# Current_Sense_-_AMS.net
KiCad netlist of a schematic drawn in Altium Designer
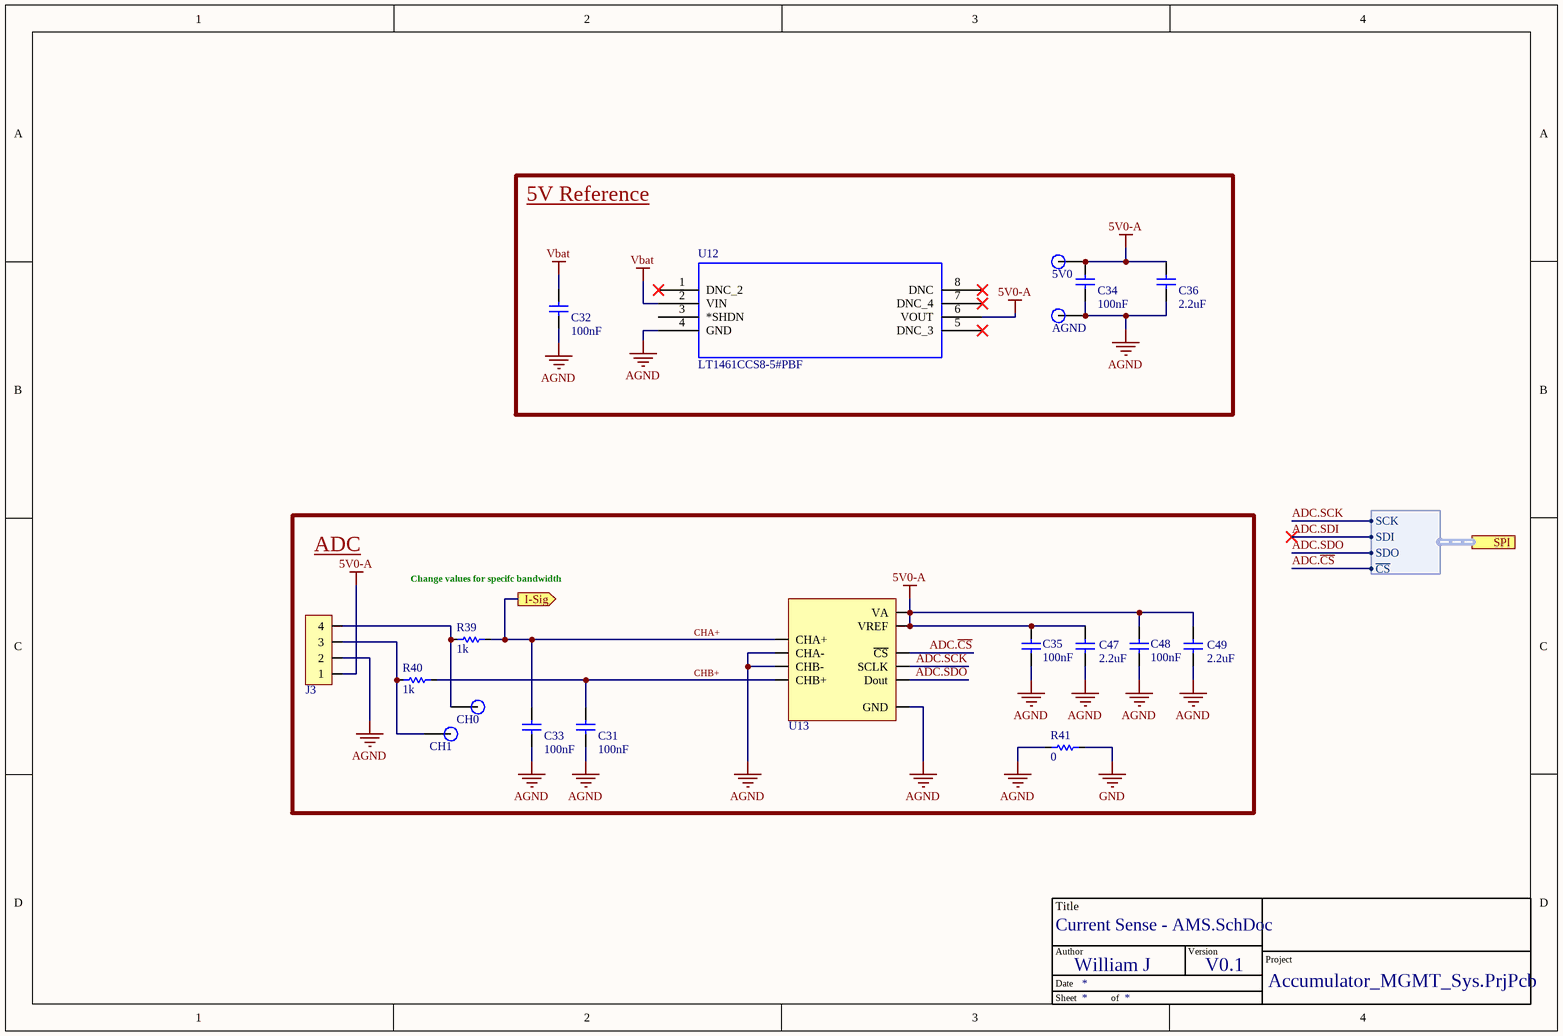
[diagram p0: Current Sense - AMS.SchDoc]

(export (version "E")
  (design (tool "Eeschema 10.0.6"))
  (components
    (comp (ref "5V0")
      (value "1.2mm Test point")
      (footprint "Test Point")
      (libsource (lib "PCHLib") (part "Test Point"))
    )
    (comp (ref "AGND")
      (value "1.2mm Test point")
      (footprint "Test Point")
      (libsource (lib "PCHLib") (part "Test Point"))
    )
    (comp (ref "C31")
      (value "100nF")
      (footprint "0402")
      (description "Capacitor")
      (fields (field (name "Comment") "C0603C104K3RAC7013"))
      (libsource (lib "Passives") (part "Capacitor"))
    )
    (comp (ref "C32")
      (value "100nF")
      (footprint "C_0603")
      (description "Capacitor")
      (fields (field (name "Comment") "C0603C104K3RAC7013"))
      (libsource (lib "Passives") (part "Capacitor"))
    )
    (comp (ref "C33")
      (value "100nF")
      (footprint "0402")
      (description "Capacitor")
      (fields (field (name "Comment") "C0603C104K3RAC7013"))
      (libsource (lib "Passives") (part "Capacitor"))
    )
    (comp (ref "C34")
      (value "100nF")
      (footprint "C_0603")
      (description "Capacitor")
      (fields (field (name "Comment") "C0603C104K3RAC7013"))
      (libsource (lib "Passives") (part "Capacitor"))
    )
    (comp (ref "C35")
      (value "100nF")
      (footprint "C_0603")
      (description "Capacitor")
      (fields (field (name "Comment") "C0603C104K3RAC7013"))
      (libsource (lib "Passives") (part "Capacitor"))
    )
    (comp (ref "C36")
      (value "2.2uF")
      (footprint "C_0603")
      (description "Capacitor")
      (fields (field (name "Comment") "CL10A225KP8NNNC"))
      (libsource (lib "Passives") (part "Capacitor"))
    )
    (comp (ref "C47")
      (value "2.2uF")
      (footprint "C_0603")
      (description "Capacitor")
      (fields (field (name "Comment") "CL10A225KP8NNNC"))
      (libsource (lib "Passives") (part "Capacitor"))
    )
    (comp (ref "C48")
      (value "100nF")
      (footprint "C_0603")
      (description "Capacitor")
      (fields (field (name "Comment") "C0603C104K3RAC7013"))
      (libsource (lib "Passives") (part "Capacitor"))
    )
    (comp (ref "C49")
      (value "2.2uF")
      (footprint "C_0603")
      (description "Capacitor")
      (fields (field (name "Comment") "CL10A225KP8NNNC"))
      (libsource (lib "Passives") (part "Capacitor"))
    )
    (comp (ref "CH0")
      (value "1.2mm Test point")
      (footprint "Test Point")
      (libsource (lib "PCHLib") (part "Test Point"))
    )
    (comp (ref "CH1")
      (value "1.2mm Test point")
      (footprint "Test Point")
      (libsource (lib "PCHLib") (part "Test Point"))
    )
    (comp (ref "J3")
      (value "3-794632-4")
      (footprint "3-794632-4")
      (description "Conn Power HDR 4 POS 3mm Solder ST Thru-Hole 4 Terminal 1 Port Box/Tray")
      (fields (field (name "MANUFACTURER") "TE Connectivity"))
      (libsource (lib "TE_Con") (part "3-794632-4"))
    )
    (comp (ref "R39")
      (value "1k")
      (footprint "R_0402")
      (description "Resistor")
      (fields (field (name "Comment") "CRT0402-DY-1001GLF"))
      (libsource (lib "Passives") (part "Resistor"))
    )
    (comp (ref "R40")
      (value "1k")
      (footprint "R_0402")
      (description "Resistor")
      (fields (field (name "Comment") "CRT0402-DY-1001GLF"))
      (libsource (lib "Passives") (part "Resistor"))
    )
    (comp (ref "R41")
      (value "0")
      (footprint "R-0603")
      (description "Resistor")
      (fields (field (name "Comment") "AC0603JR-100RL"))
      (libsource (lib "Passives") (part "Resistor"))
    )
    (comp (ref "U12")
      (value "LT1461CCS8-5#PBF")
      (footprint "LT1461ACS8-3:SO-8_S")
      (fields
        (field (name "MF") "{'manufacturer': u'Analog Devices / Linear Technology'}")
        (field (name "MP") "LT1461ACS8-3")
      )
      (libsource (lib "*") (part "LT1461ACS8-3"))
    )
    (comp (ref "U13")
      (value "ADC122S625CIMM/NOPB")
      (footprint "TSSOP50P490X110-10N")
      (description "Analog to Digital Converters - ADC Dual 50kSPS-200kSPS 12B ADC")
      (libsource (lib "PCHLib") (part "ADC122S625CIMM/NOPB"))
    )
  )
  (nets
    (net (code "2") (name "/ADC.SCK") (class "Default")
      (node (ref "U13") (pin "9") (pinfunction "SCLK_9") (pintype "passive"))
    )
    (net (code "4") (name "/ADC.SDO") (class "Default")
      (node (ref "U13") (pin "8") (pinfunction "Dout_8") (pintype "passive"))
    )
    (net (code "5") (name "/ADC.~{CS}") (class "Default")
      (node (ref "U13") (pin "10") (pinfunction "~{CS}_10") (pintype "passive"))
    )
    (net (code "6") (name "/CHA+") (class "Default")
      (node (ref "C33") (pin "2") (pinfunction "2_2") (pintype "passive"))
      (node (ref "R39") (pin "2") (pinfunction "2_2") (pintype "passive"))
      (node (ref "U13") (pin "2") (pinfunction "CHA+_2") (pintype "passive"))
    )
    (net (code "7") (name "/CHB+") (class "Default")
      (node (ref "C31") (pin "2") (pinfunction "2_2") (pintype "passive"))
      (node (ref "R40") (pin "2") (pinfunction "2_2") (pintype "passive"))
      (node (ref "U13") (pin "5") (pinfunction "CHB+_5") (pintype "passive"))
    )
    (net (code "9") (name "5V0-A") (class "Default")
      (node (ref "5V0") (pin "1") (pinfunction "1_1") (pintype "passive"))
      (node (ref "C34") (pin "2") (pinfunction "2_2") (pintype "passive"))
      (node (ref "C35") (pin "2") (pinfunction "2_2") (pintype "passive"))
      (node (ref "C36") (pin "2") (pinfunction "2_2") (pintype "passive"))
      (node (ref "C47") (pin "2") (pinfunction "2_2") (pintype "passive"))
      (node (ref "C48") (pin "2") (pinfunction "2_2") (pintype "passive"))
      (node (ref "C49") (pin "2") (pinfunction "2_2") (pintype "passive"))
      (node (ref "J3") (pin "1") (pinfunction "1_1") (pintype "passive"))
      (node (ref "U12") (pin "6") (pinfunction "VOUT_6") (pintype "passive"))
      (node (ref "U13") (pin "1") (pinfunction "VREF_1") (pintype "passive"))
      (node (ref "U13") (pin "7") (pinfunction "VA_7") (pintype "passive"))
    )
    (net (code "10") (name "AGND") (class "Default")
      (node (ref "AGND") (pin "1") (pinfunction "1_1") (pintype "passive"))
      (node (ref "C31") (pin "1") (pinfunction "1_1") (pintype "passive"))
      (node (ref "C32") (pin "1") (pinfunction "1_1") (pintype "passive"))
      (node (ref "C33") (pin "1") (pinfunction "1_1") (pintype "passive"))
      (node (ref "C34") (pin "1") (pinfunction "1_1") (pintype "passive"))
      (node (ref "C35") (pin "1") (pinfunction "1_1") (pintype "passive"))
      (node (ref "C36") (pin "1") (pinfunction "1_1") (pintype "passive"))
      (node (ref "C47") (pin "1") (pinfunction "1_1") (pintype "passive"))
      (node (ref "C48") (pin "1") (pinfunction "1_1") (pintype "passive"))
      (node (ref "C49") (pin "1") (pinfunction "1_1") (pintype "passive"))
      (node (ref "J3") (pin "2") (pinfunction "2_2") (pintype "passive"))
      (node (ref "R41") (pin "1") (pinfunction "1_1") (pintype "passive"))
      (node (ref "U12") (pin "4") (pinfunction "GND_4") (pintype "power_in"))
      (node (ref "U13") (pin "3") (pinfunction "CHA-_3") (pintype "passive"))
      (node (ref "U13") (pin "4") (pinfunction "CHB-_4") (pintype "passive"))
      (node (ref "U13") (pin "6") (pinfunction "GND_6") (pintype "passive"))
    )
    (net (code "11") (name "GND") (class "Default")
      (node (ref "R41") (pin "2") (pinfunction "2_2") (pintype "passive"))
    )
    (net (code "12") (name "Net-(CH0-Pad1)") (class "Default")
      (node (ref "CH0") (pin "1") (pinfunction "1_1") (pintype "passive"))
      (node (ref "J3") (pin "4") (pinfunction "4_4") (pintype "passive"))
      (node (ref "R39") (pin "1") (pinfunction "1_1") (pintype "passive"))
    )
    (net (code "13") (name "Net-(CH1-Pad1)") (class "Default")
      (node (ref "CH1") (pin "1") (pinfunction "1_1") (pintype "passive"))
      (node (ref "J3") (pin "3") (pinfunction "3_3") (pintype "passive"))
      (node (ref "R40") (pin "1") (pinfunction "1_1") (pintype "passive"))
    )
    (net (code "14") (name "Vbat") (class "Default")
      (node (ref "C32") (pin "2") (pinfunction "2_2") (pintype "passive"))
      (node (ref "U12") (pin "2") (pinfunction "VIN_2") (pintype "passive"))
    )
    (net (code "15") (name "unconnected-(U12-*SHDN-Pad3)") (class "Default")
      (node (ref "U12") (pin "3") (pinfunction "*SHDN_3") (pintype "passive"))
    )
    (net (code "16") (name "unconnected-(U12-DNC-Pad8)") (class "Default")
      (node (ref "U12") (pin "8") (pinfunction "DNC_8") (pintype "passive+no_connect"))
    )
    (net (code "17") (name "unconnected-(U12-DNC_2-Pad1)") (class "Default")
      (node (ref "U12") (pin "1") (pinfunction "DNC_2_1") (pintype "passive+no_connect"))
    )
    (net (code "18") (name "unconnected-(U12-DNC_3-Pad5)") (class "Default")
      (node (ref "U12") (pin "5") (pinfunction "DNC_3_5") (pintype "passive+no_connect"))
    )
    (net (code "19") (name "unconnected-(U12-DNC_4-Pad7)") (class "Default")
      (node (ref "U12") (pin "7") (pinfunction "DNC_4_7") (pintype "passive+no_connect"))
    )
  )
)
